# MCU.net
KiCad netlist of a schematic drawn in Altium Designer
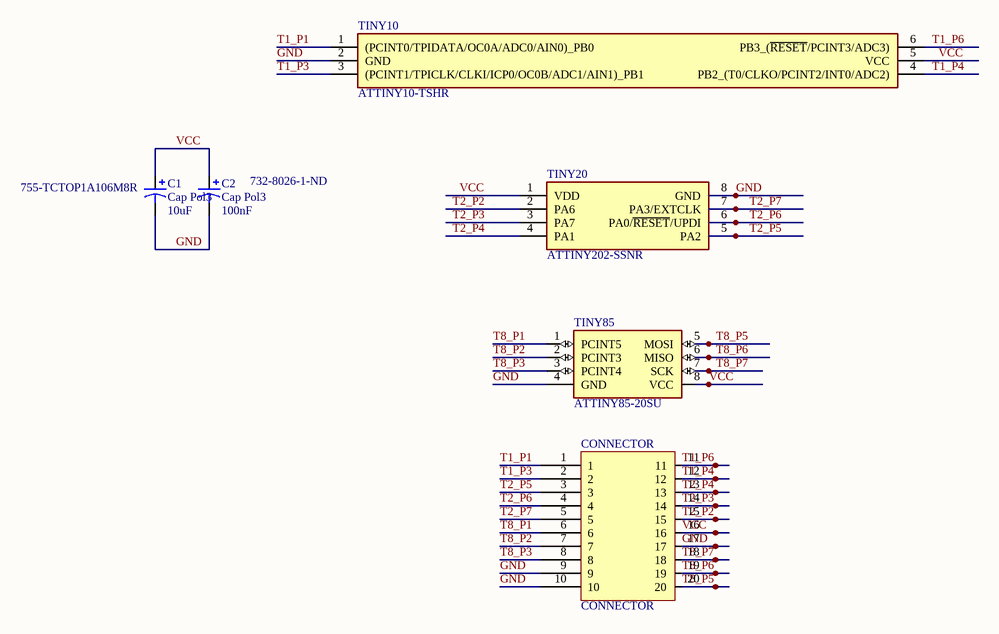
[diagram p0: MCU.SchDoc]

(export (version "E")
  (design (tool "Eeschema 10.0.6"))
  (components
    (comp (ref "C1")
      (value "Cap Pol3")
      (footprint "C0805")
      (description "Polarized Capacitor (Surface Mount)")
      (fields
        (field (name "ALTIUM_VALUE") "10uF")
        (field (name "SUPPLIER PART NUMBER 1") "755-TCTOP1A106M8R")
        (field (name "PUBLISHER") "Altium Limited")
      )
      (libsource (lib "Miscellaneous Devices") (part "Cap Pol3"))
    )
    (comp (ref "C2")
      (value "Cap Pol3")
      (footprint "C0805")
      (description "Polarized Capacitor (Surface Mount)")
      (fields
        (field (name "ALTIUM_VALUE") "100nF")
        (field (name "SUPPLIER PART NUMBER 1") "732-8026-1-ND")
        (field (name "PUBLISHER") "Altium Limited")
      )
      (libsource (lib "Miscellaneous Devices") (part "Cap Pol3"))
    )
    (comp (ref "CONNECTOR")
      (value "CONNECTOR")
      (footprint "PIN_HEADER")
      (libsource (lib "PIN_HEADER") (part "CONNECTOR"))
    )
    (comp (ref "TINY10")
      (value "ATTINY10-TSHR")
      (footprint "SamacSys:SOT95P280X145-6N")
      (description "Integrated Circuit")
      (fields
        (field (name "MOUSER PART NUMBER") "556-ATTINY10-TSHR")
        (field (name "RS PART NUMBER") "1330946P")
      )
      (libsource (lib "*") (part "ATTINY10-TSHR"))
    )
    (comp (ref "TINY20")
      (value "ATTINY202-SSNR")
      (footprint "SamacSys:SOIC127P600X175-8N")
      (description "Integrated Circuit")
      (fields (field (name "MOUSER PART NUMBER") "579-ATTINY202-SSNR"))
      (libsource (lib "*") (part "ATTINY202-SSNR"))
    )
    (comp (ref "TINY85")
      (value "ATTINY85-20SU")
      (footprint "SamacSys:SOT127P798X216-8N")
      (description "Integrated Circuit")
      (fields
        (field (name "MOUSER PART NUMBER") "556-ATTINY85-20SU")
        (field (name "RS PART NUMBER") "6962639P")
      )
      (libsource (lib "*") (part "ATTINY85-20SU"))
    )
  )
  (nets
    (net (code "1") (name "/GND") (class "Default")
      (node (ref "C1") (pin "2") (pinfunction "2_2") (pintype "passive"))
      (node (ref "C2") (pin "2") (pinfunction "2_2") (pintype "passive"))
      (node (ref "CONNECTOR") (pin "10") (pinfunction "10_10") (pintype "passive"))
      (node (ref "CONNECTOR") (pin "17") (pinfunction "17_17") (pintype "passive"))
      (node (ref "CONNECTOR") (pin "9") (pinfunction "9_9") (pintype "passive"))
      (node (ref "TINY10") (pin "2") (pinfunction "GND_2") (pintype "passive"))
      (node (ref "TINY20") (pin "8") (pinfunction "GND_8") (pintype "passive"))
      (node (ref "TINY85") (pin "4") (pinfunction "GND_4") (pintype "power_in"))
    )
    (net (code "2") (name "/T1_P1") (class "Default")
      (node (ref "CONNECTOR") (pin "1") (pinfunction "1_1") (pintype "passive"))
      (node (ref "TINY10") (pin "1") (pinfunction "(PCINT0/TPIDATA/OC0A/ADC0/AIN0)_PB0_1") (pintype "passive"))
    )
    (net (code "3") (name "/T1_P3") (class "Default")
      (node (ref "CONNECTOR") (pin "2") (pinfunction "2_2") (pintype "passive"))
      (node (ref "TINY10") (pin "3") (pinfunction "(PCINT1/TPICLK/CLKI/ICP0/OC0B/ADC1/AIN1)_PB1_3") (pintype "passive"))
    )
    (net (code "4") (name "/T1_P4") (class "Default")
      (node (ref "CONNECTOR") (pin "12") (pinfunction "12_12") (pintype "passive"))
      (node (ref "TINY10") (pin "4") (pinfunction "PB2_(T0/CLKO/PCINT2/INT0/ADC2)_4") (pintype "passive"))
    )
    (net (code "5") (name "/T1_P6") (class "Default")
      (node (ref "CONNECTOR") (pin "11") (pinfunction "11_11") (pintype "passive"))
      (node (ref "TINY10") (pin "6") (pinfunction "PB3_(~{RESET}/PCINT3/ADC3)_6") (pintype "passive"))
    )
    (net (code "6") (name "/T2_P2") (class "Default")
      (node (ref "CONNECTOR") (pin "15") (pinfunction "15_15") (pintype "passive"))
      (node (ref "TINY20") (pin "2") (pinfunction "PA6_2") (pintype "passive"))
    )
    (net (code "7") (name "/T2_P3") (class "Default")
      (node (ref "CONNECTOR") (pin "14") (pinfunction "14_14") (pintype "passive"))
      (node (ref "TINY20") (pin "3") (pinfunction "PA7_3") (pintype "passive"))
    )
    (net (code "8") (name "/T2_P4") (class "Default")
      (node (ref "CONNECTOR") (pin "13") (pinfunction "13_13") (pintype "passive"))
      (node (ref "TINY20") (pin "4") (pinfunction "PA1_4") (pintype "passive"))
    )
    (net (code "9") (name "/T2_P5") (class "Default")
      (node (ref "CONNECTOR") (pin "3") (pinfunction "3_3") (pintype "passive"))
      (node (ref "TINY20") (pin "5") (pinfunction "PA2_5") (pintype "passive"))
    )
    (net (code "10") (name "/T2_P6") (class "Default")
      (node (ref "CONNECTOR") (pin "4") (pinfunction "4_4") (pintype "passive"))
      (node (ref "TINY20") (pin "6") (pinfunction "PA0/~{RESET}/UPDI_6") (pintype "passive"))
    )
    (net (code "11") (name "/T2_P7") (class "Default")
      (node (ref "CONNECTOR") (pin "5") (pinfunction "5_5") (pintype "passive"))
      (node (ref "TINY20") (pin "7") (pinfunction "PA3/EXTCLK_7") (pintype "passive"))
    )
    (net (code "12") (name "/T8_P1") (class "Default")
      (node (ref "CONNECTOR") (pin "6") (pinfunction "6_6") (pintype "passive"))
      (node (ref "TINY85") (pin "1") (pinfunction "PCINT5_1") (pintype "bidirectional"))
    )
    (net (code "13") (name "/T8_P2") (class "Default")
      (node (ref "CONNECTOR") (pin "7") (pinfunction "7_7") (pintype "passive"))
      (node (ref "TINY85") (pin "2") (pinfunction "PCINT3_2") (pintype "bidirectional"))
    )
    (net (code "14") (name "/T8_P3") (class "Default")
      (node (ref "CONNECTOR") (pin "8") (pinfunction "8_8") (pintype "passive"))
      (node (ref "TINY85") (pin "3") (pinfunction "PCINT4_3") (pintype "bidirectional"))
    )
    (net (code "15") (name "/T8_P5") (class "Default")
      (node (ref "CONNECTOR") (pin "20") (pinfunction "20_20") (pintype "passive"))
      (node (ref "TINY85") (pin "5") (pinfunction "MOSI_5") (pintype "bidirectional"))
    )
    (net (code "16") (name "/T8_P6") (class "Default")
      (node (ref "CONNECTOR") (pin "19") (pinfunction "19_19") (pintype "passive"))
      (node (ref "TINY85") (pin "6") (pinfunction "MISO_6") (pintype "bidirectional"))
    )
    (net (code "17") (name "/T8_P7") (class "Default")
      (node (ref "CONNECTOR") (pin "18") (pinfunction "18_18") (pintype "passive"))
      (node (ref "TINY85") (pin "7") (pinfunction "SCK_7") (pintype "bidirectional"))
    )
    (net (code "18") (name "/VCC") (class "Default")
      (node (ref "C1") (pin "1") (pinfunction "1_1") (pintype "passive"))
      (node (ref "C2") (pin "1") (pinfunction "1_1") (pintype "passive"))
      (node (ref "CONNECTOR") (pin "16") (pinfunction "16_16") (pintype "passive"))
      (node (ref "TINY10") (pin "5") (pinfunction "VCC_5") (pintype "passive"))
      (node (ref "TINY20") (pin "1") (pinfunction "VDD_1") (pintype "passive"))
      (node (ref "TINY85") (pin "8") (pinfunction "VCC_8") (pintype "power_in"))
    )
  )
)
